# boardShildSchematicBACKUP.net
KiCad netlist of a schematic drawn in EAGLE
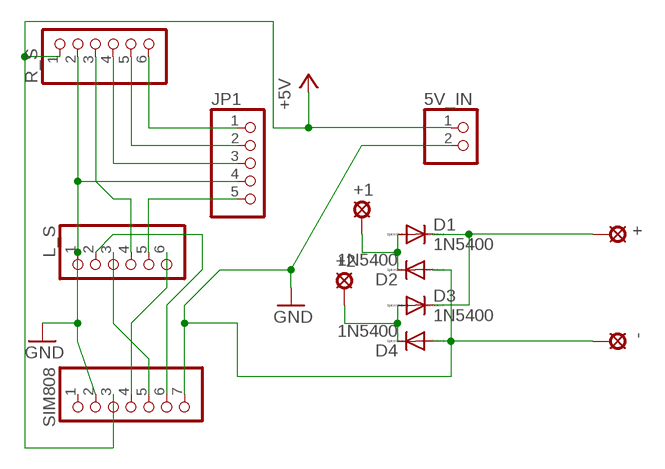
[diagram p0: schematic, sheet 1]

(export (version "E")
  (design (tool "Eeschema 10.0.6"))
  (components
    (comp (ref "+")
      (value "SE14")
      (footprint "eagle-import:SE14")
      (libsource (lib "eagle-import") (part "SE14"))
    )
    (comp (ref "+1")
      (value "SE14")
      (footprint "eagle-import:SE14")
      (libsource (lib "eagle-import") (part "SE14"))
    )
    (comp (ref "+2")
      (value "SE14")
      (footprint "eagle-import:SE14")
      (libsource (lib "eagle-import") (part "SE14"))
    )
    (comp (ref "-")
      (value "SE14")
      (footprint "eagle-import:SE14")
      (libsource (lib "eagle-import") (part "SE14"))
    )
    (comp (ref "5V_IN")
      (value "PINHD-1X2")
      (footprint "eagle-import:1X02")
      (libsource (lib "eagle-import") (part "PINHD-1X2"))
    )
    (comp (ref "D1")
      (value "1N5400")
      (footprint "eagle-import:DO201-15")
      (libsource (lib "eagle-import") (part "1N5400"))
    )
    (comp (ref "D2")
      (value "1N5400")
      (footprint "eagle-import:DO201-15")
      (libsource (lib "eagle-import") (part "1N5400"))
    )
    (comp (ref "D3")
      (value "1N5400")
      (footprint "eagle-import:DO201-15")
      (libsource (lib "eagle-import") (part "1N5400"))
    )
    (comp (ref "D4")
      (value "1N5400")
      (footprint "eagle-import:DO201-15")
      (libsource (lib "eagle-import") (part "1N5400"))
    )
    (comp (ref "JP1")
      (value "PINHD-1X5")
      (footprint "eagle-import:1X05")
      (libsource (lib "eagle-import") (part "PINHD-1X5"))
    )
    (comp (ref "L_S")
      (value "PINHD-1X6")
      (footprint "eagle-import:1X06")
      (libsource (lib "eagle-import") (part "PINHD-1X6"))
    )
    (comp (ref "R_S")
      (value "PINHD-1X6")
      (footprint "eagle-import:1X06")
      (libsource (lib "eagle-import") (part "PINHD-1X6"))
    )
    (comp (ref "SIM808")
      (value "PINHD-1X7")
      (footprint "eagle-import:1X07")
      (libsource (lib "eagle-import") (part "PINHD-1X7"))
    )
  )
  (nets
    (net (code "1") (name "+5V") (class "Default")
      (node (ref "5V_IN") (pin "1") (pinfunction "1_1") (pintype "passive"))
      (node (ref "R_S") (pin "1") (pinfunction "1_1") (pintype "passive"))
      (node (ref "SIM808") (pin "3") (pinfunction "3_3") (pintype "passive"))
    )
    (net (code "2") (name "GND") (class "Default")
      (node (ref "-") (pin "MP") (pinfunction "MP_MP") (pintype "passive"))
      (node (ref "5V_IN") (pin "2") (pinfunction "2_2") (pintype "passive"))
      (node (ref "D2") (pin "A") (pinfunction "A_A") (pintype "passive"))
      (node (ref "D4") (pin "A") (pinfunction "A_A") (pintype "passive"))
      (node (ref "JP1") (pin "4") (pinfunction "4_4") (pintype "passive"))
      (node (ref "L_S") (pin "1") (pinfunction "1_1") (pintype "passive"))
      (node (ref "R_S") (pin "2") (pinfunction "2_2") (pintype "passive"))
      (node (ref "SIM808") (pin "2") (pinfunction "2_2") (pintype "passive"))
      (node (ref "SIM808") (pin "7") (pinfunction "7_7") (pintype "passive"))
    )
    (net (code "3") (name "Net-(+-PadMP)") (class "Default")
      (node (ref "+") (pin "MP") (pinfunction "MP_MP") (pintype "passive"))
      (node (ref "D1") (pin "C") (pinfunction "C_C") (pintype "passive"))
      (node (ref "D3") (pin "C") (pinfunction "C_C") (pintype "passive"))
    )
    (net (code "4") (name "Net-(+1-PadMP)") (class "Default")
      (node (ref "+1") (pin "MP") (pinfunction "MP_MP") (pintype "passive"))
      (node (ref "D1") (pin "A") (pinfunction "A_A") (pintype "passive"))
      (node (ref "D2") (pin "C") (pinfunction "C_C") (pintype "passive"))
    )
    (net (code "5") (name "Net-(+2-PadMP)") (class "Default")
      (node (ref "+2") (pin "MP") (pinfunction "MP_MP") (pintype "passive"))
      (node (ref "D3") (pin "A") (pinfunction "A_A") (pintype "passive"))
      (node (ref "D4") (pin "C") (pinfunction "C_C") (pintype "passive"))
    )
    (net (code "6") (name "Net-(JP1-Pad1)") (class "Default")
      (node (ref "JP1") (pin "1") (pinfunction "1_1") (pintype "passive"))
      (node (ref "R_S") (pin "6") (pinfunction "6_6") (pintype "passive"))
    )
    (net (code "7") (name "Net-(JP1-Pad2)") (class "Default")
      (node (ref "JP1") (pin "2") (pinfunction "2_2") (pintype "passive"))
      (node (ref "R_S") (pin "5") (pinfunction "5_5") (pintype "passive"))
    )
    (net (code "8") (name "Net-(JP1-Pad3)") (class "Default")
      (node (ref "JP1") (pin "3") (pinfunction "3_3") (pintype "passive"))
      (node (ref "R_S") (pin "4") (pinfunction "4_4") (pintype "passive"))
    )
    (net (code "9") (name "Net-(JP1-Pad5)") (class "Default")
      (node (ref "JP1") (pin "5") (pinfunction "5_5") (pintype "passive"))
      (node (ref "L_S") (pin "5") (pinfunction "5_5") (pintype "passive"))
    )
    (net (code "10") (name "Net-(L_S-Pad2)") (class "Default")
      (node (ref "L_S") (pin "2") (pinfunction "2_2") (pintype "passive"))
      (node (ref "SIM808") (pin "6") (pinfunction "6_6") (pintype "passive"))
    )
    (net (code "11") (name "Net-(L_S-Pad3)") (class "Default")
      (node (ref "L_S") (pin "3") (pinfunction "3_3") (pintype "passive"))
      (node (ref "SIM808") (pin "5") (pinfunction "5_5") (pintype "passive"))
    )
    (net (code "12") (name "Net-(L_S-Pad4)") (class "Default")
      (node (ref "L_S") (pin "4") (pinfunction "4_4") (pintype "passive"))
      (node (ref "R_S") (pin "3") (pinfunction "3_3") (pintype "passive"))
    )
    (net (code "13") (name "Net-(L_S-Pad6)") (class "Default")
      (node (ref "L_S") (pin "6") (pinfunction "6_6") (pintype "passive"))
      (node (ref "SIM808") (pin "4") (pinfunction "4_4") (pintype "passive"))
    )
    (net (code "14") (name "unconnected-(SIM808-Pad1)") (class "Default")
      (node (ref "SIM808") (pin "1") (pinfunction "1_1") (pintype "passive"))
    )
  )
)
